# untitled.net
KiCad netlist of a schematic drawn in EAGLE
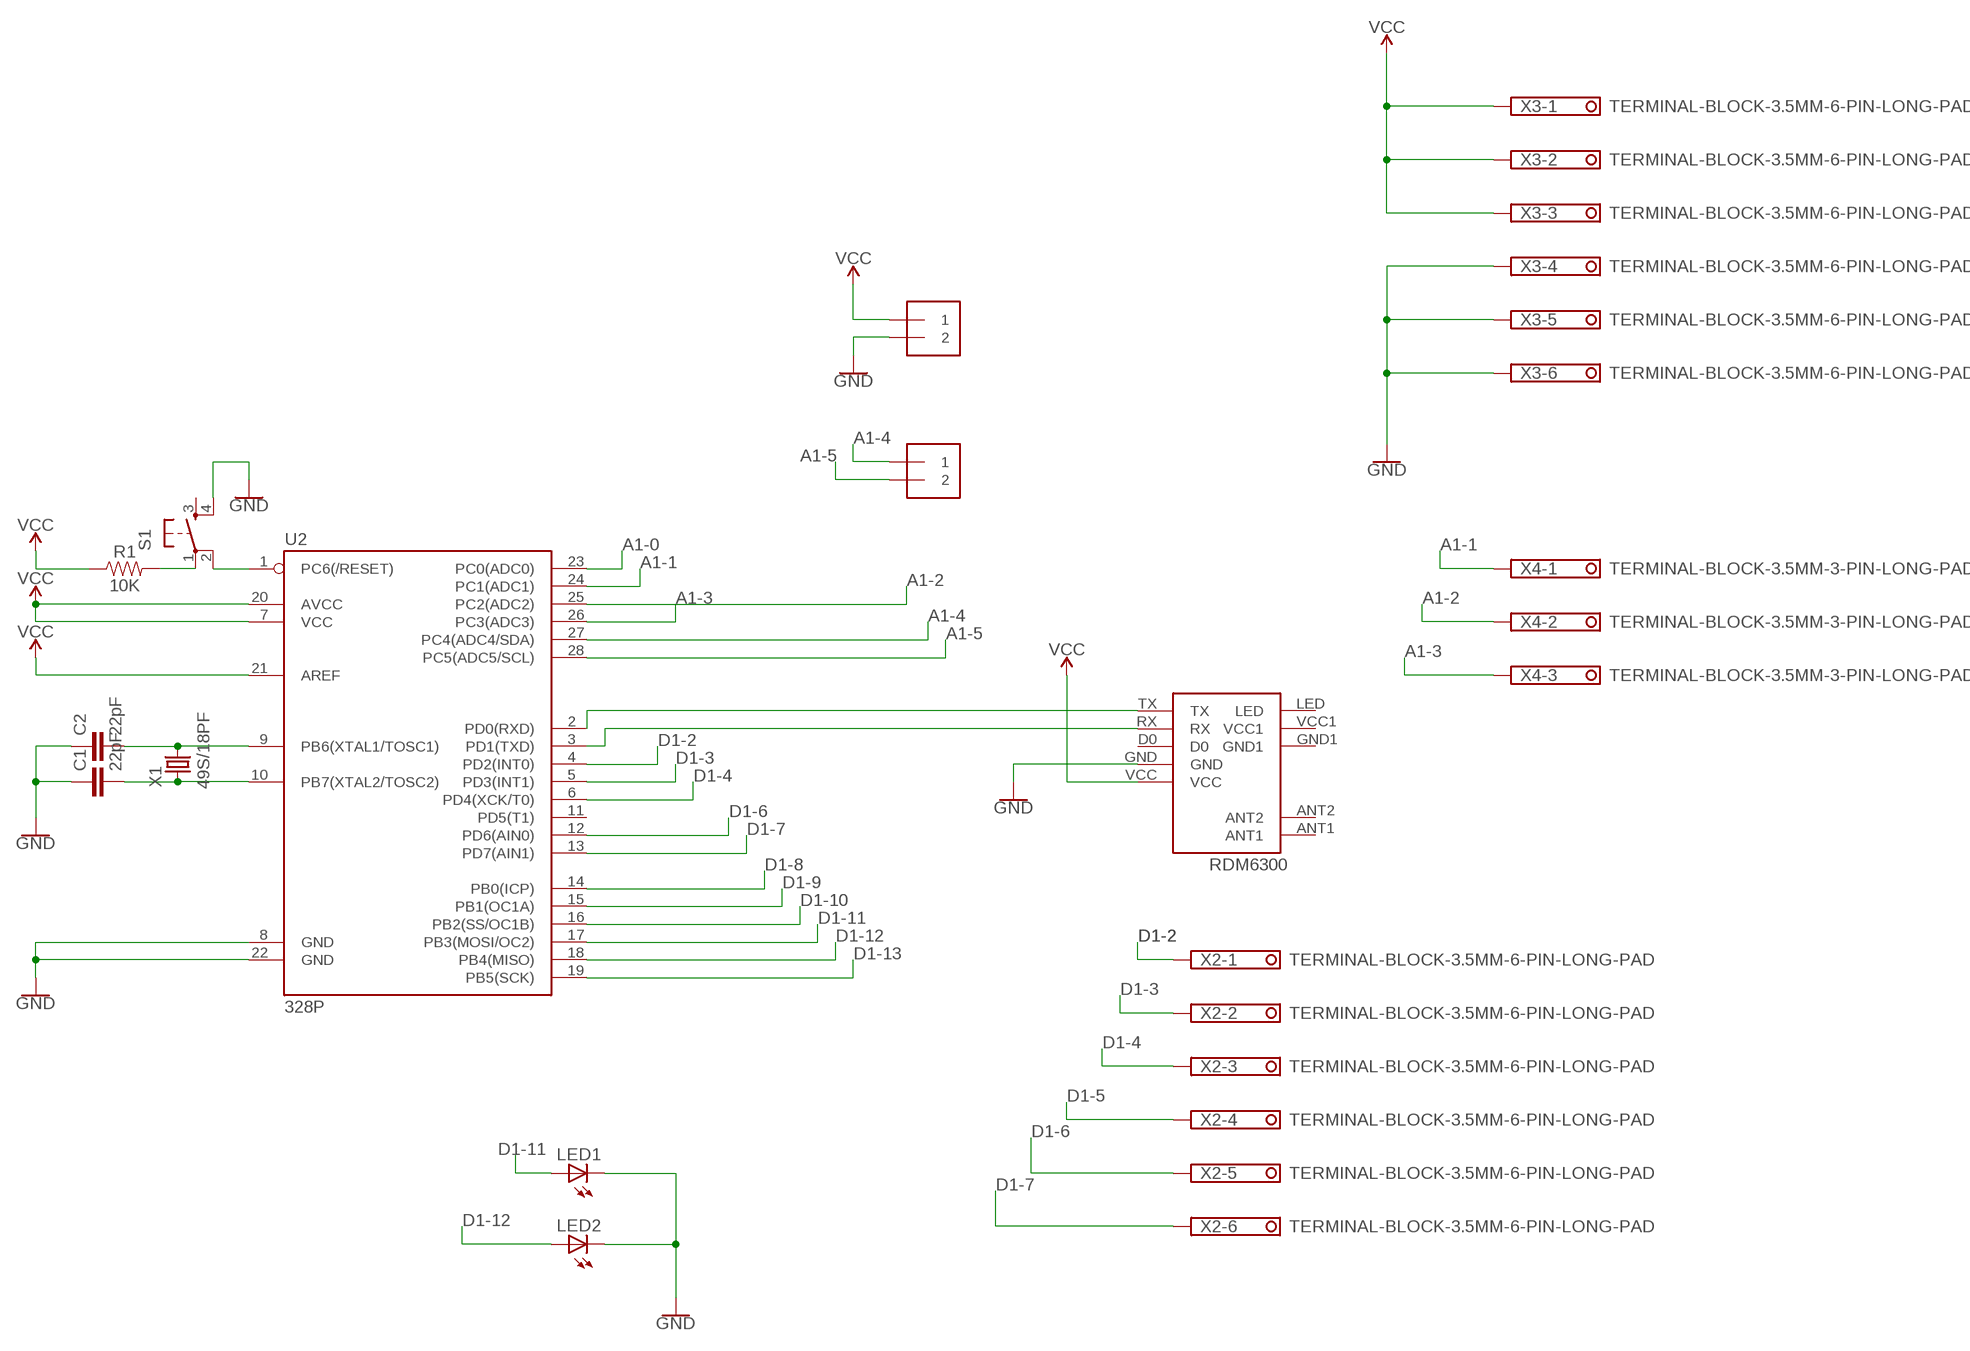
[diagram p0: schematic, sheet 1]

(export (version "E")
  (design (tool "Eeschema 10.0.6"))
  (components
    (comp (ref "C1")
      (value "22pF")
      (footprint "eagle-import:CAP-PTH-2.54")
      (libsource (lib "eagle-import") (part "22PF-PTH-2.54MM-200V-5%"))
    )
    (comp (ref "C2")
      (value "22pF")
      (footprint "eagle-import:CAP-PTH-2.54")
      (libsource (lib "eagle-import") (part "22PF-PTH-2.54MM-200V-5%"))
    )
    (comp (ref "J1")
      (value "1X2-3.5MM")
      (footprint "eagle-import:1X2-3.5MM")
      (libsource (lib "eagle-import") (part "1X2-3.5MM"))
    )
    (comp (ref "J2")
      (value "1X2-3.5MM")
      (footprint "eagle-import:1X2-3.5MM")
      (libsource (lib "eagle-import") (part "1X2-3.5MM"))
    )
    (comp (ref "LED1")
      (value "LED5MM")
      (footprint "eagle-import:LED5MM")
      (libsource (lib "eagle-import") (part "LED5MM"))
    )
    (comp (ref "LED2")
      (value "LED5MM")
      (footprint "eagle-import:LED5MM")
      (libsource (lib "eagle-import") (part "LED5MM"))
    )
    (comp (ref "R1")
      (value "10K")
      (footprint "eagle-import:AXIAL-0.3")
      (libsource (lib "eagle-import") (part "10MOHM-HORIZ-1/4W-5%"))
    )
    (comp (ref "RDM1")
      (value "RDM6300")
      (footprint "eagle-import:RDM6300")
      (libsource (lib "eagle-import") (part "RDM6300"))
    )
    (comp (ref "S1")
      (value "TAC_SWITCHPTH")
      (footprint "eagle-import:TACTILE-PTH")
      (libsource (lib "eagle-import") (part "TAC_SWITCHPTH"))
    )
    (comp (ref "U2")
      (value "328P")
      (footprint "eagle-import:DIP28")
      (libsource (lib "eagle-import") (part "ATMEGA328P_PDIP"))
    )
    (comp (ref "X1")
      (value "49S/18PF")
      (footprint "eagle-import:XTAL_HC49")
      (fields (field (name "MANUFACTURER") "Xinhunjing ") (field (name "CREATED_BY") "PCBLayout.com"))
      (libsource (lib "eagle-import") (part "49S/18PF"))
    )
    (comp (ref "X2")
      (value "TERMINAL-BLOCK-3.5MM-6-PIN-LONG-PAD")
      (footprint "eagle-import:TERMINAL-BLOCK-6-PIN-3.5MM-LONG-PAD")
      (libsource (lib "eagle-import") (part "TERMINAL-BLOCK-3.5MM-6-PIN-LONG-PAD"))
    )
    (comp (ref "X3")
      (value "TERMINAL-BLOCK-3.5MM-6-PIN-LONG-PAD")
      (footprint "eagle-import:TERMINAL-BLOCK-6-PIN-3.5MM-LONG-PAD")
      (libsource (lib "eagle-import") (part "TERMINAL-BLOCK-3.5MM-6-PIN-LONG-PAD"))
    )
    (comp (ref "X4")
      (value "TERMINAL-BLOCK-3.5MM-3-PIN-LONG-PAD")
      (footprint "eagle-import:TERMINAL-BLOCK-3-PIN-3.5MM-LONG-PAD")
      (libsource (lib "eagle-import") (part "TERMINAL-BLOCK-3.5MM-3-PIN-LONG-PAD"))
    )
  )
  (nets
    (net (code "1") (name "/A1-0") (class "Default")
      (node (ref "U2") (pin "23") (pinfunction "PC0(ADC0)_23") (pintype "bidirectional"))
    )
    (net (code "2") (name "/A1-1") (class "Default")
      (node (ref "U2") (pin "24") (pinfunction "PC1(ADC1)_24") (pintype "bidirectional"))
      (node (ref "X4") (pin "1") (pinfunction "K_1") (pintype "passive"))
    )
    (net (code "3") (name "/A1-2") (class "Default")
      (node (ref "U2") (pin "25") (pinfunction "PC2(ADC2)_25") (pintype "bidirectional"))
      (node (ref "X4") (pin "2") (pinfunction "K_2") (pintype "passive"))
    )
    (net (code "4") (name "/A1-3") (class "Default")
      (node (ref "U2") (pin "26") (pinfunction "PC3(ADC3)_26") (pintype "bidirectional"))
      (node (ref "X4") (pin "3") (pinfunction "K_3") (pintype "passive"))
    )
    (net (code "5") (name "/A1-4") (class "Default")
      (node (ref "J2") (pin "1") (pinfunction "1_1") (pintype "passive"))
      (node (ref "U2") (pin "27") (pinfunction "PC4(ADC4/SDA)_27") (pintype "bidirectional"))
    )
    (net (code "6") (name "/A1-5") (class "Default")
      (node (ref "J2") (pin "2") (pinfunction "2_2") (pintype "passive"))
      (node (ref "U2") (pin "28") (pinfunction "PC5(ADC5/SCL)_28") (pintype "bidirectional"))
    )
    (net (code "7") (name "/D1-2") (class "Default")
      (node (ref "U2") (pin "4") (pinfunction "PD2(INT0)_4") (pintype "bidirectional"))
      (node (ref "X2") (pin "1") (pinfunction "K_1") (pintype "passive"))
    )
    (net (code "8") (name "/D1-3") (class "Default")
      (node (ref "U2") (pin "5") (pinfunction "PD3(INT1)_5") (pintype "bidirectional"))
      (node (ref "X2") (pin "2") (pinfunction "K_2") (pintype "passive"))
    )
    (net (code "9") (name "/D1-4") (class "Default")
      (node (ref "U2") (pin "6") (pinfunction "PD4(XCK/T0)_6") (pintype "bidirectional"))
      (node (ref "X2") (pin "3") (pinfunction "K_3") (pintype "passive"))
    )
    (net (code "10") (name "/D1-5") (class "Default")
      (node (ref "X2") (pin "4") (pinfunction "K_4") (pintype "passive"))
    )
    (net (code "11") (name "/D1-6") (class "Default")
      (node (ref "U2") (pin "12") (pinfunction "PD6(AIN0)_12") (pintype "bidirectional"))
      (node (ref "X2") (pin "5") (pinfunction "K_5") (pintype "passive"))
    )
    (net (code "12") (name "/D1-7") (class "Default")
      (node (ref "U2") (pin "13") (pinfunction "PD7(AIN1)_13") (pintype "bidirectional"))
      (node (ref "X2") (pin "6") (pinfunction "K_6") (pintype "passive"))
    )
    (net (code "13") (name "/D1-8") (class "Default")
      (node (ref "U2") (pin "14") (pinfunction "PB0(ICP)_14") (pintype "bidirectional"))
    )
    (net (code "14") (name "/D1-9") (class "Default")
      (node (ref "U2") (pin "15") (pinfunction "PB1(OC1A)_15") (pintype "bidirectional"))
    )
    (net (code "15") (name "/D1-10") (class "Default")
      (node (ref "U2") (pin "16") (pinfunction "PB2(SS/OC1B)_16") (pintype "bidirectional"))
    )
    (net (code "16") (name "/D1-11") (class "Default")
      (node (ref "LED1") (pin "A") (pinfunction "A_A") (pintype "passive"))
      (node (ref "U2") (pin "17") (pinfunction "PB3(MOSI/OC2)_17") (pintype "bidirectional"))
    )
    (net (code "17") (name "/D1-12") (class "Default")
      (node (ref "LED2") (pin "A") (pinfunction "A_A") (pintype "passive"))
      (node (ref "U2") (pin "18") (pinfunction "PB4(MISO)_18") (pintype "bidirectional"))
    )
    (net (code "18") (name "/D1-13") (class "Default")
      (node (ref "U2") (pin "19") (pinfunction "PB5(SCK)_19") (pintype "bidirectional"))
    )
    (net (code "19") (name "GND") (class "Default")
      (node (ref "C1") (pin "1") (pinfunction "1_1") (pintype "passive"))
      (node (ref "C2") (pin "1") (pinfunction "1_1") (pintype "passive"))
      (node (ref "J1") (pin "2") (pinfunction "2_2") (pintype "passive"))
      (node (ref "LED1") (pin "K") (pinfunction "C_K") (pintype "passive"))
      (node (ref "LED2") (pin "K") (pinfunction "C_K") (pintype "passive"))
      (node (ref "RDM1") (pin "GND") (pinfunction "GND_GND") (pintype "bidirectional"))
      (node (ref "S1") (pin "4") (pinfunction "4_4") (pintype "passive"))
      (node (ref "U2") (pin "22") (pinfunction "GND_22") (pintype "bidirectional"))
      (node (ref "U2") (pin "8") (pinfunction "GND_8") (pintype "bidirectional"))
      (node (ref "X3") (pin "4") (pinfunction "K_4") (pintype "passive"))
      (node (ref "X3") (pin "5") (pinfunction "K_5") (pintype "passive"))
      (node (ref "X3") (pin "6") (pinfunction "K_6") (pintype "passive"))
    )
    (net (code "20") (name "Net-(R1-2)") (class "Default")
      (node (ref "R1") (pin "P$2") (pinfunction "2_P$2") (pintype "passive"))
      (node (ref "S1") (pin "1") (pinfunction "1_1") (pintype "passive"))
    )
    (net (code "21") (name "Net-(U2-PB6(XTAL1{slash}TOSC1))") (class "Default")
      (node (ref "C2") (pin "2") (pinfunction "2_2") (pintype "passive"))
      (node (ref "U2") (pin "9") (pinfunction "PB6(XTAL1/TOSC1)_9") (pintype "bidirectional"))
      (node (ref "X1") (pin "2") (pinfunction "2_2") (pintype "passive"))
    )
    (net (code "22") (name "Net-(U2-PB7(XTAL2{slash}TOSC2))") (class "Default")
      (node (ref "C1") (pin "2") (pinfunction "2_2") (pintype "passive"))
      (node (ref "U2") (pin "10") (pinfunction "PB7(XTAL2/TOSC2)_10") (pintype "bidirectional"))
      (node (ref "X1") (pin "1") (pinfunction "1_1") (pintype "passive"))
    )
    (net (code "23") (name "Net-(U2-PC6({slash}RESET))") (class "Default")
      (node (ref "S1") (pin "2") (pinfunction "2_2") (pintype "passive"))
      (node (ref "U2") (pin "1") (pinfunction "PC6(/RESET)_1") (pintype "bidirectional"))
    )
    (net (code "24") (name "Net-(U2-PD0(RXD))") (class "Default")
      (node (ref "RDM1") (pin "TX") (pinfunction "TX_TX") (pintype "bidirectional"))
      (node (ref "U2") (pin "2") (pinfunction "PD0(RXD)_2") (pintype "bidirectional"))
    )
    (net (code "25") (name "Net-(U2-PD1(TXD))") (class "Default")
      (node (ref "RDM1") (pin "RX") (pinfunction "RX_RX") (pintype "bidirectional"))
      (node (ref "U2") (pin "3") (pinfunction "PD1(TXD)_3") (pintype "bidirectional"))
    )
    (net (code "26") (name "VCC") (class "Default")
      (node (ref "J1") (pin "1") (pinfunction "1_1") (pintype "passive"))
      (node (ref "R1") (pin "P$1") (pinfunction "1_P$1") (pintype "passive"))
      (node (ref "RDM1") (pin "VCC") (pinfunction "VCC_VCC") (pintype "bidirectional"))
      (node (ref "U2") (pin "20") (pinfunction "AVCC_20") (pintype "bidirectional"))
      (node (ref "U2") (pin "21") (pinfunction "AREF_21") (pintype "bidirectional"))
      (node (ref "U2") (pin "7") (pinfunction "VCC_7") (pintype "bidirectional"))
      (node (ref "X3") (pin "1") (pinfunction "K_1") (pintype "passive"))
      (node (ref "X3") (pin "2") (pinfunction "K_2") (pintype "passive"))
      (node (ref "X3") (pin "3") (pinfunction "K_3") (pintype "passive"))
    )
    (net (code "27") (name "unconnected-(RDM1-PadANT1)") (class "Default")
      (node (ref "RDM1") (pin "ANT1") (pinfunction "ANT1_ANT1") (pintype "bidirectional"))
    )
    (net (code "28") (name "unconnected-(RDM1-PadANT2)") (class "Default")
      (node (ref "RDM1") (pin "ANT2") (pinfunction "ANT2_ANT2") (pintype "bidirectional"))
    )
    (net (code "29") (name "unconnected-(RDM1-PadD0)") (class "Default")
      (node (ref "RDM1") (pin "D0") (pinfunction "D0_D0") (pintype "bidirectional"))
    )
    (net (code "30") (name "unconnected-(RDM1-PadGND1)") (class "Default")
      (node (ref "RDM1") (pin "GND1") (pinfunction "GND1_GND1") (pintype "bidirectional"))
    )
    (net (code "31") (name "unconnected-(RDM1-PadLED)") (class "Default")
      (node (ref "RDM1") (pin "LED") (pinfunction "LED_LED") (pintype "bidirectional"))
    )
    (net (code "32") (name "unconnected-(RDM1-PadVCC1)") (class "Default")
      (node (ref "RDM1") (pin "VCC1") (pinfunction "VCC1_VCC1") (pintype "bidirectional"))
    )
    (net (code "33") (name "unconnected-(S1-Pad3)") (class "Default")
      (node (ref "S1") (pin "3") (pinfunction "3_3") (pintype "passive"))
    )
    (net (code "34") (name "unconnected-(U2-PD5(T1)-Pad11)") (class "Default")
      (node (ref "U2") (pin "11") (pinfunction "PD5(T1)_11") (pintype "bidirectional"))
    )
  )
)
